# Main.net
KiCad netlist of a schematic drawn in Altium Designer
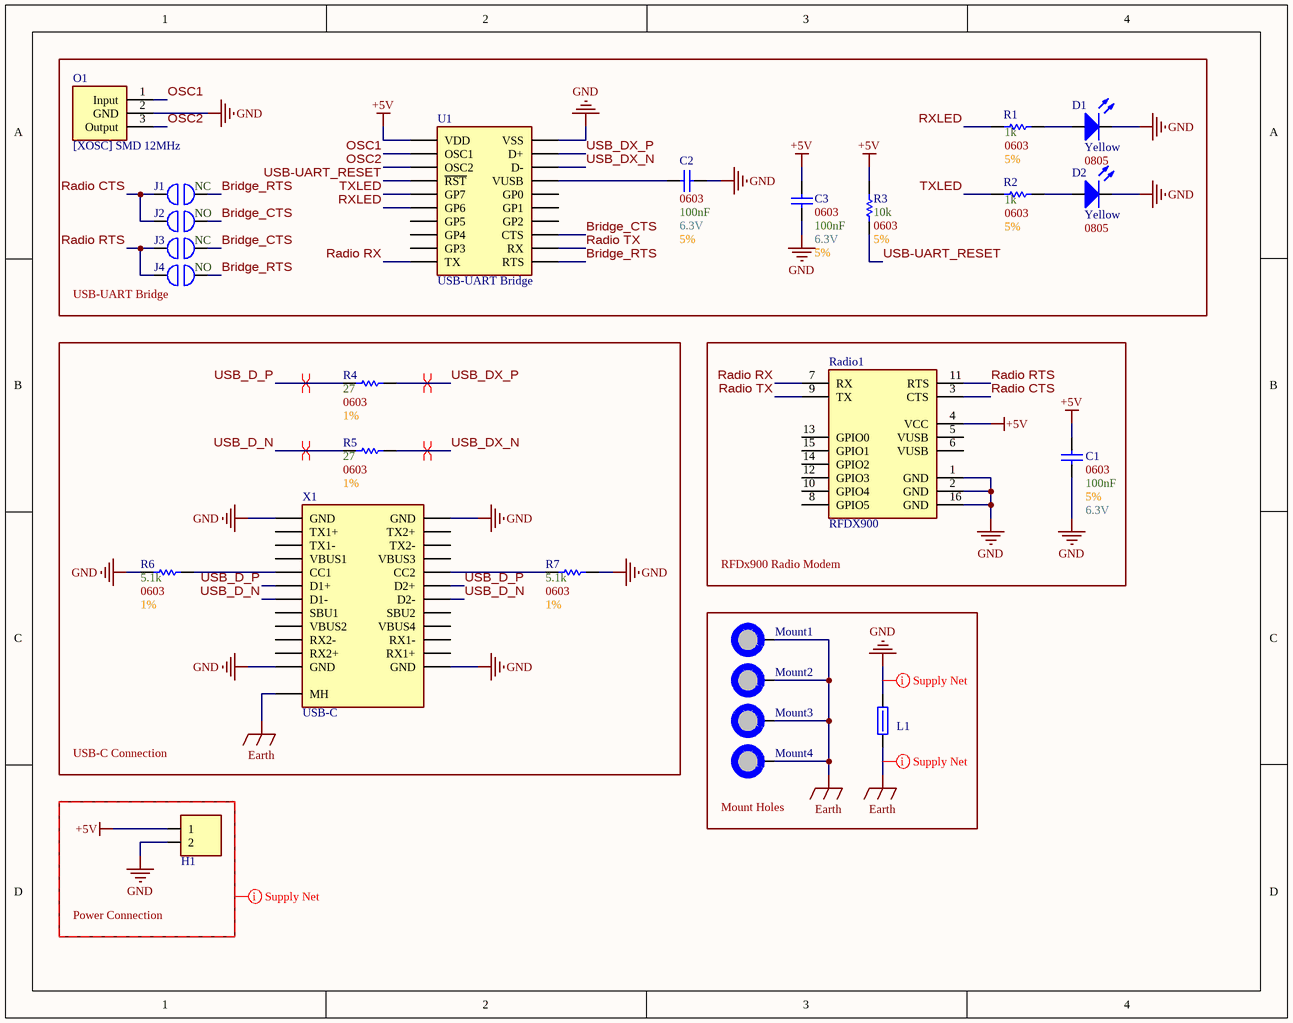
[diagram p0: Main.SchDoc]

(export (version "E")
  (design (tool "Eeschema 10.0.6"))
  (components
    (comp (ref "C1")
      (value "[Cap] SMD Nonpolarized")
      (footprint "[Cap] SMD 0603")
      (fields
        (field (name "SIZE PACKAGE") "0603")
        (field (name "CAPACITANCE") "100nF")
        (field (name "VOLTAGE") "6.3V")
        (field (name "TOLERANCE") "5%")
      )
      (libsource (lib "RADM Components") (part "[Cap] SMD Nonpolarized"))
    )
    (comp (ref "C2")
      (value "[Cap] SMD Nonpolarized")
      (footprint "[Cap] SMD 0603")
      (fields
        (field (name "SIZE PACKAGE") "0603")
        (field (name "CAPACITANCE") "100nF")
        (field (name "VOLTAGE") "6.3V")
        (field (name "TOLERANCE") "5%")
      )
      (libsource (lib "RADM Components") (part "[Cap] SMD Nonpolarized"))
    )
    (comp (ref "C3")
      (value "[Cap] SMD Nonpolarized")
      (footprint "[Cap] SMD 0603")
      (fields
        (field (name "SIZE PACKAGE") "0603")
        (field (name "CAPACITANCE") "100nF")
        (field (name "VOLTAGE") "6.3V")
        (field (name "TOLERANCE") "5%")
      )
      (libsource (lib "RADM Components") (part "[Cap] SMD Nonpolarized"))
    )
    (comp (ref "D1")
      (value "SMD LED")
      (footprint "[LED] SMD 0805")
      (description "Generic")
      (fields (field (name "COLOR") "Yellow") (field (name "SIZE PACKAGE") "0805"))
      (libsource (lib "RADM Components") (part "[LED] SMD"))
    )
    (comp (ref "D2")
      (value "SMD LED")
      (footprint "[LED] SMD 0805")
      (description "Generic")
      (fields (field (name "COLOR") "Yellow") (field (name "SIZE PACKAGE") "0805"))
      (libsource (lib "RADM Components") (part "[LED] SMD"))
    )
    (comp (ref "H1")
      (value "1x2 Male")
      (footprint "[Header] Shrouded 1x2 Male")
      (description "0705430036\r\nMates with 0050579402")
      (libsource (lib "RADM Connectors") (part "[Header] Shrouded 1x2 Male"))
    )
    (comp (ref "J1")
      (value "[Jump] SMD Jumper")
      (footprint "[Jumper] Solderable Jumper")
      (description "Solderable jumper")
      (fields (field (name "NO/NC") "NC"))
      (libsource (lib "RADM Components") (part "[Jump] SMD Jumper"))
    )
    (comp (ref "J2")
      (value "[Jump] SMD Jumper")
      (footprint "[Jumper] Solderable Jumper")
      (description "Solderable jumper")
      (fields (field (name "NO/NC") "NO"))
      (libsource (lib "RADM Components") (part "[Jump] SMD Jumper"))
    )
    (comp (ref "J3")
      (value "[Jump] SMD Jumper")
      (footprint "[Jumper] Solderable Jumper")
      (description "Solderable jumper")
      (fields (field (name "NO/NC") "NC"))
      (libsource (lib "RADM Components") (part "[Jump] SMD Jumper"))
    )
    (comp (ref "J4")
      (value "[Jump] SMD Jumper")
      (footprint "[Jumper] Solderable Jumper")
      (description "Solderable jumper")
      (fields (field (name "NO/NC") "NO"))
      (libsource (lib "RADM Components") (part "[Jump] SMD Jumper"))
    )
    (comp (ref "L1")
      (value "652-MH2029-300Y")
      (footprint "[Ferrite] SMD Bead 0805 (1)")
      (libsource (lib "RADM Components") (part "[Ferrite] SMD Ferrite Bead (1)"))
    )
    (comp (ref "Mount1")
      (value "M3 Mount Hole")
      (footprint "[Mount] M3 Mount Hole")
      (description "Place at least 4.5mm from board edge. Plated.")
      (libsource (lib "RADM Connectors") (part "[Mount] M3 Mount Hole"))
    )
    (comp (ref "Mount2")
      (value "M3 Mount Hole")
      (footprint "[Mount] M3 Mount Hole")
      (description "Place at least 4.5mm from board edge. Plated.")
      (libsource (lib "RADM Connectors") (part "[Mount] M3 Mount Hole"))
    )
    (comp (ref "Mount3")
      (value "M3 Mount Hole")
      (footprint "[Mount] M3 Mount Hole")
      (description "Place at least 4.5mm from board edge. Plated.")
      (libsource (lib "RADM Connectors") (part "[Mount] M3 Mount Hole"))
    )
    (comp (ref "Mount4")
      (value "M3 Mount Hole")
      (footprint "[Mount] M3 Mount Hole")
      (description "Place at least 4.5mm from board edge. Plated.")
      (libsource (lib "RADM Connectors") (part "[Mount] M3 Mount Hole"))
    )
    (comp (ref "O1")
      (value "[XOSC] SMD 12MHz")
      (footprint "[XOSC] SMD 12MHz")
      (libsource (lib "RADM Components") (part "[XOSC] SMD 12MHz"))
    )
    (comp (ref "R1")
      (value "[Res] SMD Resistor")
      (footprint "[Res] SMD 0603")
      (description "Generic")
      (fields
        (field (name "RESISTANCE") "1k")
        (field (name "SIZE PACKAGE") "0603")
        (field (name "TOLERANCE") "5%")
      )
      (libsource (lib "RADM Components") (part "[Res] SMD Resistor"))
    )
    (comp (ref "R2")
      (value "[Res] SMD Resistor")
      (footprint "[Res] SMD 0603")
      (description "Generic")
      (fields
        (field (name "RESISTANCE") "1k")
        (field (name "SIZE PACKAGE") "0603")
        (field (name "TOLERANCE") "5%")
      )
      (libsource (lib "RADM Components") (part "[Res] SMD Resistor"))
    )
    (comp (ref "R3")
      (value "[Res] SMD Resistor")
      (footprint "[Res] SMD 0603")
      (description "Generic")
      (fields
        (field (name "RESISTANCE") "10k")
        (field (name "SIZE PACKAGE") "0603")
        (field (name "TOLERANCE") "5%")
      )
      (libsource (lib "RADM Components") (part "[Res] SMD Resistor"))
    )
    (comp (ref "R4")
      (value "[Res] SMD Resistor")
      (footprint "[Res] SMD 0603")
      (description "Generic")
      (fields
        (field (name "TOLERANCE") "1%")
        (field (name "RESISTANCE") "27")
        (field (name "SIZE PACKAGE") "0603")
      )
      (libsource (lib "RADM Components") (part "[Res] SMD Resistor"))
    )
    (comp (ref "R5")
      (value "[Res] SMD Resistor")
      (footprint "[Res] SMD 0603")
      (description "Generic")
      (fields
        (field (name "TOLERANCE") "1%")
        (field (name "RESISTANCE") "27")
        (field (name "SIZE PACKAGE") "0603")
      )
      (libsource (lib "RADM Components") (part "[Res] SMD Resistor"))
    )
    (comp (ref "R6")
      (value "[Res] SMD Resistor")
      (footprint "[Res] SMD 0603")
      (description "Generic")
      (fields
        (field (name "TOLERANCE") "1%")
        (field (name "RESISTANCE") "5.1k")
        (field (name "SIZE PACKAGE") "0603")
      )
      (libsource (lib "RADM Components") (part "[Res] SMD Resistor"))
    )
    (comp (ref "R7")
      (value "[Res] SMD Resistor")
      (footprint "[Res] SMD 0603")
      (description "Generic")
      (fields
        (field (name "TOLERANCE") "1%")
        (field (name "RESISTANCE") "5.1k")
        (field (name "SIZE PACKAGE") "0603")
      )
      (libsource (lib "RADM Components") (part "[Res] SMD Resistor"))
    )
    (comp (ref "Radio1")
      (value "RFDX900")
      (footprint "[Device] RFDX900 Radio SMD Mount")
      (description "RFDX900 Long-Range RF Module")
      (libsource (lib "RADM Components") (part "[Device] RFDX900 Radio"))
    )
    (comp (ref "U1")
      (value "USB-UART Bridge")
      (footprint "[IC] USB-UART Bridge")
      (description "MCP2200T-I/SO")
      (libsource (lib "RADM Components") (part "[IC] USB-UART Bridge"))
    )
    (comp (ref "X1")
      (value "USB-C")
      (footprint "[Port] USB-C")
      (libsource (lib "RADM Connectors") (part "[Port] USB Type-C"))
    )
  )
  (nets
    (net (code "1") (name "+5V") (class "Default")
      (node (ref "C1") (pin "2") (pinfunction "2_2") (pintype "passive"))
      (node (ref "C3") (pin "2") (pinfunction "2_2") (pintype "passive"))
      (node (ref "H1") (pin "1") (pinfunction "1_1") (pintype "passive"))
      (node (ref "R3") (pin "2") (pinfunction "2_2") (pintype "passive"))
      (node (ref "Radio1") (pin "4") (pinfunction "VCC_4") (pintype "passive"))
      (node (ref "U1") (pin "1") (pinfunction "VDD_1") (pintype "passive"))
    )
    (net (code "2") (name "/Bridge_CTS") (class "Default")
      (node (ref "J2") (pin "2") (pintype "passive"))
      (node (ref "J3") (pin "2") (pintype "passive"))
      (node (ref "U1") (pin "13") (pinfunction "CTS_13") (pintype "passive"))
    )
    (net (code "3") (name "/Bridge_RTS") (class "Default")
      (node (ref "J1") (pin "2") (pintype "passive"))
      (node (ref "J4") (pin "2") (pintype "passive"))
      (node (ref "U1") (pin "11") (pinfunction "RTS_11") (pintype "passive"))
    )
    (net (code "4") (name "/OSC1") (class "Default")
      (node (ref "O1") (pin "1") (pinfunction "Input_1") (pintype "passive"))
      (node (ref "U1") (pin "2") (pinfunction "OSC1_2") (pintype "passive"))
    )
    (net (code "5") (name "/OSC2") (class "Default")
      (node (ref "O1") (pin "3") (pinfunction "Output_3") (pintype "passive"))
      (node (ref "U1") (pin "3") (pinfunction "OSC2_3") (pintype "passive"))
    )
    (net (code "6") (name "/RXLED") (class "Default")
      (node (ref "R1") (pin "2") (pinfunction "2_2") (pintype "passive"))
      (node (ref "U1") (pin "6") (pinfunction "GP6_6") (pintype "passive"))
    )
    (net (code "7") (name "/Radio CTS") (class "Default")
      (node (ref "J1") (pin "1") (pintype "passive"))
      (node (ref "J2") (pin "1") (pintype "passive"))
      (node (ref "Radio1") (pin "3") (pinfunction "CTS_3") (pintype "passive"))
    )
    (net (code "8") (name "/Radio RTS") (class "Default")
      (node (ref "J3") (pin "1") (pintype "passive"))
      (node (ref "J4") (pin "1") (pintype "passive"))
      (node (ref "Radio1") (pin "11") (pinfunction "RTS_11") (pintype "passive"))
    )
    (net (code "9") (name "/Radio RX") (class "Default")
      (node (ref "Radio1") (pin "7") (pinfunction "RX_7") (pintype "passive"))
      (node (ref "U1") (pin "10") (pinfunction "TX_10") (pintype "passive"))
    )
    (net (code "10") (name "/Radio TX") (class "Default")
      (node (ref "Radio1") (pin "9") (pinfunction "TX_9") (pintype "passive"))
      (node (ref "U1") (pin "12") (pinfunction "RX_12") (pintype "passive"))
    )
    (net (code "11") (name "/TXLED") (class "Default")
      (node (ref "R2") (pin "2") (pinfunction "2_2") (pintype "passive"))
      (node (ref "U1") (pin "5") (pinfunction "GP7_5") (pintype "passive"))
    )
    (net (code "12") (name "/USB-UART_RESET") (class "Default")
      (node (ref "R3") (pin "1") (pinfunction "1_1") (pintype "passive"))
      (node (ref "U1") (pin "4") (pinfunction "RST_4") (pintype "passive"))
    )
    (net (code "13") (name "/USB_DX_N") (class "Default")
      (node (ref "R5") (pin "2") (pinfunction "2_2") (pintype "passive"))
      (node (ref "U1") (pin "18") (pinfunction "D-_18") (pintype "passive"))
    )
    (net (code "14") (name "/USB_DX_P") (class "Default")
      (node (ref "R4") (pin "2") (pinfunction "2_2") (pintype "passive"))
      (node (ref "U1") (pin "19") (pinfunction "D+_19") (pintype "passive"))
    )
    (net (code "15") (name "/USB_D_N") (class "Default")
      (node (ref "R5") (pin "1") (pinfunction "1_1") (pintype "passive"))
      (node (ref "X1") (pin "A7") (pinfunction "D1-_A7") (pintype "passive"))
      (node (ref "X1") (pin "B7") (pinfunction "D2-_B7") (pintype "passive"))
    )
    (net (code "16") (name "/USB_D_P") (class "Default")
      (node (ref "R4") (pin "1") (pinfunction "1_1") (pintype "passive"))
      (node (ref "X1") (pin "A6") (pinfunction "D1+_A6") (pintype "passive"))
      (node (ref "X1") (pin "B6") (pinfunction "D2+_B6") (pintype "passive"))
    )
    (net (code "17") (name "Earth") (class "Default")
      (node (ref "L1") (pin "1") (pinfunction "1_1") (pintype "passive"))
      (node (ref "Mount1") (pin "1") (pintype "power_in"))
      (node (ref "Mount2") (pin "1") (pintype "power_in"))
      (node (ref "Mount3") (pin "1") (pintype "power_in"))
      (node (ref "Mount4") (pin "1") (pintype "power_in"))
      (node (ref "X1") (pin "MH") (pinfunction "MH_MH") (pintype "passive"))
    )
    (net (code "18") (name "GND") (class "Default")
      (node (ref "C1") (pin "1") (pinfunction "1_1") (pintype "passive"))
      (node (ref "C2") (pin "1") (pinfunction "1_1") (pintype "passive"))
      (node (ref "C3") (pin "1") (pinfunction "1_1") (pintype "passive"))
      (node (ref "D1") (pin "2") (pinfunction "Cathode_2") (pintype "passive"))
      (node (ref "D2") (pin "2") (pinfunction "Cathode_2") (pintype "passive"))
      (node (ref "H1") (pin "2") (pinfunction "2_2") (pintype "passive"))
      (node (ref "L1") (pin "2") (pinfunction "2_2") (pintype "passive"))
      (node (ref "O1") (pin "2") (pinfunction "GND_2") (pintype "passive"))
      (node (ref "R6") (pin "1") (pinfunction "1_1") (pintype "passive"))
      (node (ref "R7") (pin "2") (pinfunction "2_2") (pintype "passive"))
      (node (ref "Radio1") (pin "1") (pinfunction "GND_1") (pintype "passive"))
      (node (ref "Radio1") (pin "16") (pinfunction "GND_16") (pintype "passive"))
      (node (ref "Radio1") (pin "2") (pinfunction "GND_2") (pintype "passive"))
      (node (ref "U1") (pin "20") (pinfunction "VSS_20") (pintype "passive"))
      (node (ref "X1") (pin "A1") (pinfunction "GND_A1") (pintype "passive"))
      (node (ref "X1") (pin "A12") (pinfunction "GND_A12") (pintype "passive"))
      (node (ref "X1") (pin "B1") (pinfunction "GND_B1") (pintype "passive"))
      (node (ref "X1") (pin "B12") (pinfunction "GND_B12") (pintype "passive"))
    )
    (net (code "19") (name "Net-(D1-Anode)") (class "Default")
      (node (ref "D1") (pin "1") (pinfunction "Anode_1") (pintype "passive"))
      (node (ref "R1") (pin "1") (pinfunction "1_1") (pintype "passive"))
    )
    (net (code "20") (name "Net-(D2-Anode)") (class "Default")
      (node (ref "D2") (pin "1") (pinfunction "Anode_1") (pintype "passive"))
      (node (ref "R2") (pin "1") (pinfunction "1_1") (pintype "passive"))
    )
    (net (code "21") (name "Net-(U1-VUSB)") (class "Default")
      (node (ref "C2") (pin "2") (pinfunction "2_2") (pintype "passive"))
      (node (ref "U1") (pin "17") (pinfunction "VUSB_17") (pintype "passive"))
    )
    (net (code "22") (name "Net-(X1-CC1)") (class "Default")
      (node (ref "R6") (pin "2") (pinfunction "2_2") (pintype "passive"))
      (node (ref "X1") (pin "A5") (pinfunction "CC1_A5") (pintype "passive"))
    )
    (net (code "23") (name "Net-(X1-CC2)") (class "Default")
      (node (ref "R7") (pin "1") (pinfunction "1_1") (pintype "passive"))
      (node (ref "X1") (pin "B5") (pinfunction "CC2_B5") (pintype "passive"))
    )
    (net (code "24") (name "unconnected-(Radio1-GPIO0-Pad13)") (class "Default")
      (node (ref "Radio1") (pin "13") (pinfunction "GPIO0_13") (pintype "passive"))
    )
    (net (code "25") (name "unconnected-(Radio1-GPIO1-Pad15)") (class "Default")
      (node (ref "Radio1") (pin "15") (pinfunction "GPIO1_15") (pintype "passive"))
    )
    (net (code "26") (name "unconnected-(Radio1-GPIO2-Pad14)") (class "Default")
      (node (ref "Radio1") (pin "14") (pinfunction "GPIO2_14") (pintype "passive"))
    )
    (net (code "27") (name "unconnected-(Radio1-GPIO3-Pad12)") (class "Default")
      (node (ref "Radio1") (pin "12") (pinfunction "GPIO3_12") (pintype "passive"))
    )
    (net (code "28") (name "unconnected-(Radio1-GPIO4-Pad10)") (class "Default")
      (node (ref "Radio1") (pin "10") (pinfunction "GPIO4_10") (pintype "passive"))
    )
    (net (code "29") (name "unconnected-(Radio1-GPIO5-Pad8)") (class "Default")
      (node (ref "Radio1") (pin "8") (pinfunction "GPIO5_8") (pintype "passive"))
    )
    (net (code "30") (name "unconnected-(Radio1-VUSB-Pad5)") (class "Default")
      (node (ref "Radio1") (pin "5") (pinfunction "VUSB_5") (pintype "passive"))
    )
    (net (code "31") (name "unconnected-(Radio1-VUSB-Pad6)") (class "Default")
      (node (ref "Radio1") (pin "6") (pinfunction "VUSB_6") (pintype "passive"))
    )
    (net (code "32") (name "unconnected-(U1-GP0-Pad16)") (class "Default")
      (node (ref "U1") (pin "16") (pinfunction "GP0_16") (pintype "passive"))
    )
    (net (code "33") (name "unconnected-(U1-GP1-Pad15)") (class "Default")
      (node (ref "U1") (pin "15") (pinfunction "GP1_15") (pintype "passive"))
    )
    (net (code "34") (name "unconnected-(U1-GP2-Pad14)") (class "Default")
      (node (ref "U1") (pin "14") (pinfunction "GP2_14") (pintype "passive"))
    )
    (net (code "35") (name "unconnected-(U1-GP3-Pad9)") (class "Default")
      (node (ref "U1") (pin "9") (pinfunction "GP3_9") (pintype "passive"))
    )
    (net (code "36") (name "unconnected-(U1-GP4-Pad8)") (class "Default")
      (node (ref "U1") (pin "8") (pinfunction "GP4_8") (pintype "passive"))
    )
    (net (code "37") (name "unconnected-(U1-GP5-Pad7)") (class "Default")
      (node (ref "U1") (pin "7") (pinfunction "GP5_7") (pintype "passive"))
    )
    (net (code "38") (name "unconnected-(X1-RX1+-PadB11)") (class "Default")
      (node (ref "X1") (pin "B11") (pinfunction "RX1+_B11") (pintype "passive"))
    )
    (net (code "39") (name "unconnected-(X1-RX1--PadB10)") (class "Default")
      (node (ref "X1") (pin "B10") (pinfunction "RX1-_B10") (pintype "passive"))
    )
    (net (code "40") (name "unconnected-(X1-RX2+-PadA11)") (class "Default")
      (node (ref "X1") (pin "A11") (pinfunction "RX2+_A11") (pintype "passive"))
    )
    (net (code "41") (name "unconnected-(X1-RX2--PadA10)") (class "Default")
      (node (ref "X1") (pin "A10") (pinfunction "RX2-_A10") (pintype "passive"))
    )
    (net (code "42") (name "unconnected-(X1-SBU1-PadA8)") (class "Default")
      (node (ref "X1") (pin "A8") (pinfunction "SBU1_A8") (pintype "passive"))
    )
    (net (code "43") (name "unconnected-(X1-SBU2-PadB8)") (class "Default")
      (node (ref "X1") (pin "B8") (pinfunction "SBU2_B8") (pintype "passive"))
    )
    (net (code "44") (name "unconnected-(X1-TX1+-PadA2)") (class "Default")
      (node (ref "X1") (pin "A2") (pinfunction "TX1+_A2") (pintype "passive"))
    )
    (net (code "45") (name "unconnected-(X1-TX1--PadA3)") (class "Default")
      (node (ref "X1") (pin "A3") (pinfunction "TX1-_A3") (pintype "passive"))
    )
    (net (code "46") (name "unconnected-(X1-TX2+-PadB2)") (class "Default")
      (node (ref "X1") (pin "B2") (pinfunction "TX2+_B2") (pintype "passive"))
    )
    (net (code "47") (name "unconnected-(X1-TX2--PadB3)") (class "Default")
      (node (ref "X1") (pin "B3") (pinfunction "TX2-_B3") (pintype "passive"))
    )
    (net (code "48") (name "unconnected-(X1-VBUS1-PadA4)") (class "Default")
      (node (ref "X1") (pin "A4") (pinfunction "VBUS1_A4") (pintype "passive"))
    )
    (net (code "49") (name "unconnected-(X1-VBUS2-PadA9)") (class "Default")
      (node (ref "X1") (pin "A9") (pinfunction "VBUS2_A9") (pintype "passive"))
    )
    (net (code "50") (name "unconnected-(X1-VBUS3-PadB4)") (class "Default")
      (node (ref "X1") (pin "B4") (pinfunction "VBUS3_B4") (pintype "passive"))
    )
    (net (code "51") (name "unconnected-(X1-VBUS4-PadB9)") (class "Default")
      (node (ref "X1") (pin "B9") (pinfunction "VBUS4_B9") (pintype "passive"))
    )
  )
)
